# Controller.net
KiCad netlist of a schematic drawn in Altium Designer
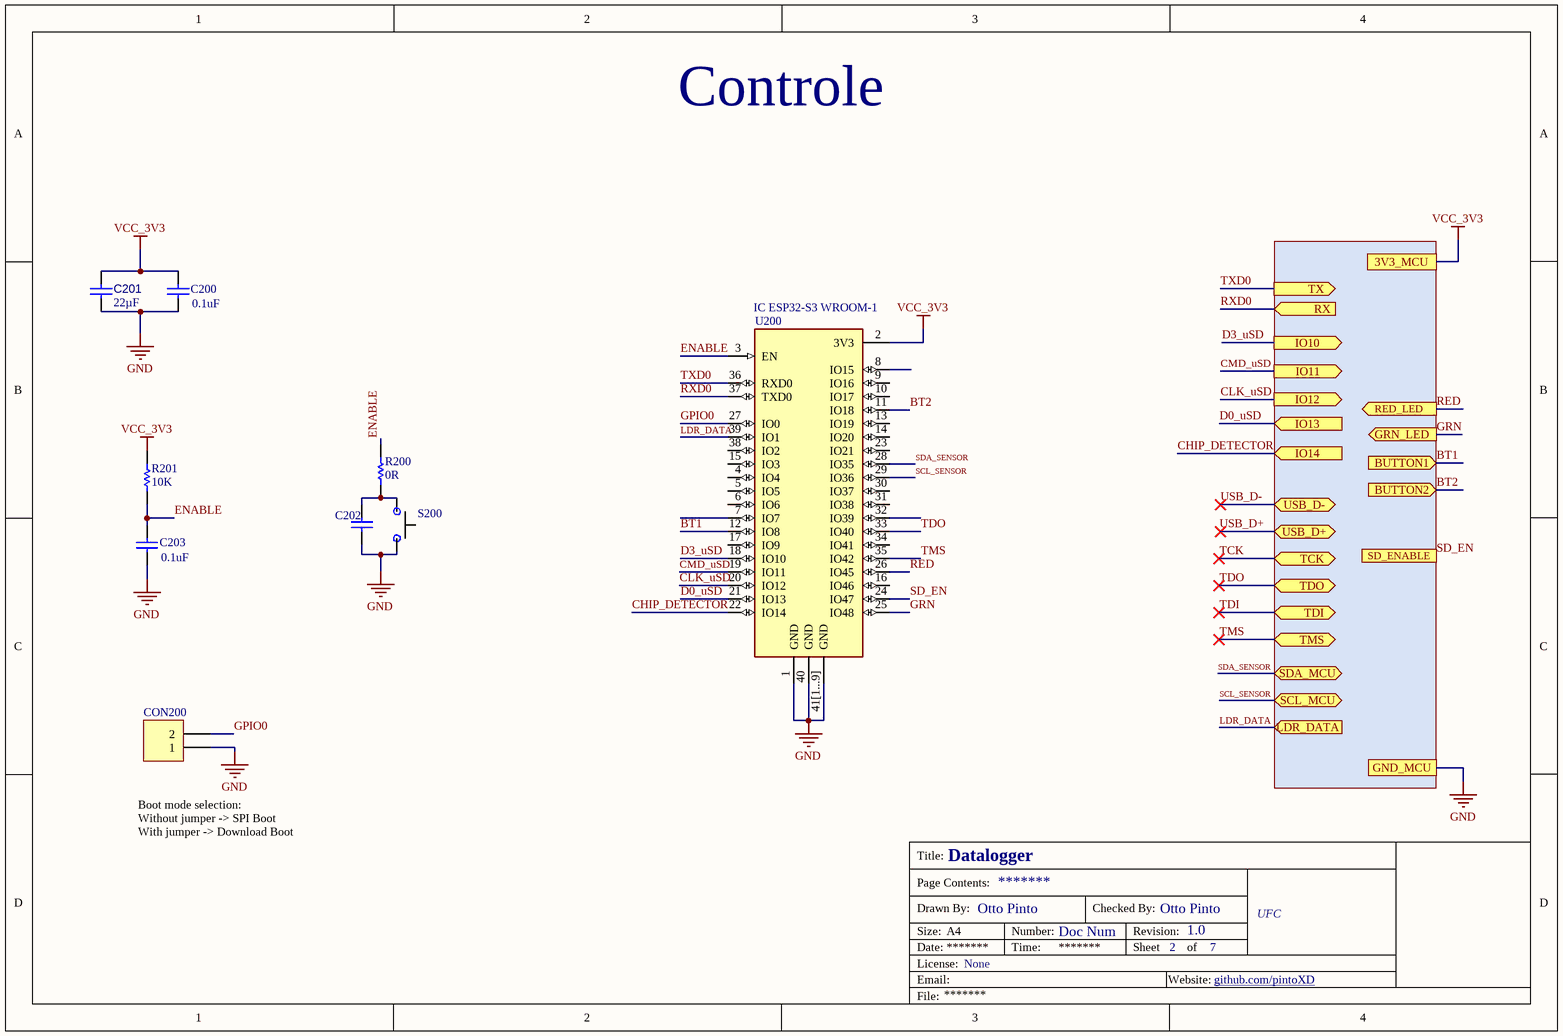
[diagram p0: Controller.SchDoc]

(export (version "E")
  (design (tool "Eeschema 10.0.6"))
  (components
    (comp (ref "C200")
      (value "0.1uF")
      (footprint "CC2012-0805")
      (description "Cap Ceramic 0.1uF 25V X7R 10% SMD 0805 125C Plastic T/R")
      (fields
        (field (name "MANUFACTURER") "KEMET")
        (field (name "MANUFACTURER PART NUMBER") "C0805C104K3RACTU")
      )
      (libsource (lib "lib_datalogger") (part "CAP CER 0.1uF 25V 0805 SMD"))
    )
    (comp (ref "C201")
      (value "22µF")
      (footprint "CC2012-0805")
      (description "Chip Capacitor, 22µF +/-40%, 16V, 0805, Thickness 1.45 mm")
      (fields (field (name "TOLERANCE") "5%") (field (name "Comment") "Capacitor 22µF +/-40% 16V 0805"))
      (libsource (lib "Mobit Brasil Ltda") (part "CAP-NP-2"))
    )
    (comp (ref "C202")
      (value "CAP CER 0.1uF 100V X7R SMD 0805")
      (footprint "CC2012-0805")
      (description "Cap Ceramic 0.1uF 25V X7R 10% SMD 0805 125C Plastic T/R")
      (fields
        (field (name "MANUFACTURER") "KEMET")
        (field (name "MANUFACTURER PART NUMBER") "C0805C104K3RACTU")
      )
      (libsource (lib "lib_datalogger") (part "CAP CER 0.1uF 25V 0805 SMD"))
    )
    (comp (ref "C203")
      (value "0.1uF")
      (footprint "CC2012-0805")
      (description "Cap Ceramic 0.1uF 25V X7R 10% SMD 0805 125C Plastic T/R")
      (fields
        (field (name "MANUFACTURER") "KEMET")
        (field (name "MANUFACTURER PART NUMBER") "C0805C104K3RACTU")
      )
      (libsource (lib "lib_datalogger") (part "CAP CER 0.1uF 25V 0805 SMD"))
    )
    (comp (ref "CON200")
      (value "PIN HEADER 2POS")
      (footprint "FP-TSW-102-07-G-S-MFG")
      (description "Conn Unshrouded Header HDR 2 POS 2.54mm Solder ST Top Entry Thru-Hole Bulk")
      (fields (field (name "MANUFACTURER PART NUMBER") "TSW-102-07-G-S"))
      (libsource (lib "Mobit Brasil Ltda") (part "Pin Header 2POS"))
    )
    (comp (ref "R200")
      (value "0R")
      (footprint "RESC2013X50X35ML15T15")
      (description "Chip Resistor, 0 Ohm, +/- 1%, 125 mW, -55 to 155 degC, 0805 (2012 Metric)")
      (fields (field (name "POWER") "125mW") (field (name "TOLERANCE") "1%"))
      (libsource (lib "Mobit Brasil Ltda") (part "RES-2"))
    )
    (comp (ref "R201")
      (value "10K")
      (footprint "CR2012-0805")
      (description "RES 0805 10K Ohm 0.1% 1/10W  SMD")
      (fields
        (field (name "MANUFACTURER PART NUMBER") "ERJ-6ENF1002V")
        (field (name "MANUFACTURER") "Panasonic Electronic Components")
        (field (name "SOURCE") "mits.SchLib")
      )
      (libsource (lib "Mobit Brasil Ltda") (part "Symbol"))
    )
    (comp (ref "S200")
      (value "SWITCH TACTILE SPST-NO 0.05A 12V SMD")
      (footprint "SWITCH_TACTILE_SMD_2PIN")
      (description "Switch Tactile N.O. SPST Rectangular Button J-Lead 0.05A 12VDC 2.55N SMD T/R")
      (fields
        (field (name "MANUFACTURER PART NUMBER") "TL3302BF260QJ")
        (field (name "MANUFACTURER") "E-Switch")
        (field (name "SOURCE") "mits.SchLib")
      )
      (libsource (lib "Mobit Brasil Ltda") (part "SWITCH TACTILE SPST-NO 0.05A 12V SMD"))
    )
    (comp (ref "U200")
      (value "IC ESP32-S3 WROOM-1")
      (footprint "ESP32_S3_WROOM_1")
      (description "SMD Module, ESP32-S3R2 With 8 MB of Flash")
      (fields
        (field (name "MF") "Espressif Systems")
        (field (name "MANUFACTURER PART NUMBER") "ESP32-S3-WROOM-1-N8")
      )
      (libsource (lib "lib_datalogger") (part "IC ESP32 S3 WROOM-1_v2"))
    )
  )
  (nets
    (net (code "1") (name "/BT1") (class "Default")
      (node (ref "U200") (pin "12") (pinfunction "IO8_12") (pintype "bidirectional"))
    )
    (net (code "2") (name "/BT2") (class "Default")
      (node (ref "U200") (pin "11") (pinfunction "IO18_11") (pintype "bidirectional"))
    )
    (net (code "3") (name "/CHIP_DETECTOR") (class "Default")
      (node (ref "U200") (pin "22") (pinfunction "IO14_22") (pintype "bidirectional"))
    )
    (net (code "4") (name "/CLK_uSD") (class "Default")
      (node (ref "U200") (pin "20") (pinfunction "IO12_20") (pintype "bidirectional"))
    )
    (net (code "5") (name "/CMD_uSD") (class "Default")
      (node (ref "U200") (pin "19") (pinfunction "IO11_19") (pintype "bidirectional"))
    )
    (net (code "6") (name "/D0_uSD") (class "Default")
      (node (ref "U200") (pin "21") (pinfunction "IO13_21") (pintype "bidirectional"))
    )
    (net (code "7") (name "/D3_uSD") (class "Default")
      (node (ref "U200") (pin "18") (pinfunction "IO10_18") (pintype "bidirectional"))
    )
    (net (code "8") (name "/ENABLE") (class "Default")
      (node (ref "C203") (pin "2") (pinfunction "2_2") (pintype "passive"))
      (node (ref "R200") (pin "2") (pinfunction "2_2") (pintype "passive"))
      (node (ref "R201") (pin "1") (pinfunction "1_1") (pintype "passive"))
      (node (ref "U200") (pin "3") (pinfunction "EN_3") (pintype "input"))
    )
    (net (code "9") (name "/GPIO0") (class "Default")
      (node (ref "CON200") (pin "2") (pinfunction "2_2") (pintype "passive"))
      (node (ref "U200") (pin "27") (pinfunction "IO0_27") (pintype "bidirectional"))
    )
    (net (code "10") (name "/GRN") (class "Default")
      (node (ref "U200") (pin "25") (pinfunction "IO48_25") (pintype "bidirectional"))
    )
    (net (code "11") (name "/LDR_DATA") (class "Default")
      (node (ref "U200") (pin "39") (pinfunction "IO1_39") (pintype "bidirectional"))
    )
    (net (code "12") (name "/RED") (class "Default")
      (node (ref "U200") (pin "26") (pinfunction "IO45_26") (pintype "bidirectional"))
    )
    (net (code "13") (name "/RXD0") (class "Default")
      (node (ref "U200") (pin "37") (pinfunction "TXD0_37") (pintype "bidirectional"))
    )
    (net (code "14") (name "/SCL_SENSOR") (class "Default")
      (node (ref "U200") (pin "29") (pinfunction "IO36_29") (pintype "bidirectional"))
    )
    (net (code "15") (name "/SDA_SENSOR") (class "Default")
      (node (ref "U200") (pin "28") (pinfunction "IO35_28") (pintype "bidirectional"))
    )
    (net (code "16") (name "/SD_EN") (class "Default")
      (node (ref "U200") (pin "24") (pinfunction "IO47_24") (pintype "bidirectional"))
    )
    (net (code "19") (name "/TDO") (class "Default")
      (node (ref "U200") (pin "33") (pinfunction "IO40_33") (pintype "bidirectional"))
    )
    (net (code "20") (name "/TMS") (class "Default")
      (node (ref "U200") (pin "35") (pinfunction "IO42_35") (pintype "bidirectional+no_connect"))
    )
    (net (code "21") (name "/TXD0") (class "Default")
      (node (ref "U200") (pin "36") (pinfunction "RXD0_36") (pintype "bidirectional"))
    )
    (net (code "24") (name "GND") (class "Default")
      (node (ref "C200") (pin "1") (pinfunction "1_1") (pintype "passive"))
      (node (ref "C201") (pin "1") (pinfunction "1_1") (pintype "passive"))
      (node (ref "C202") (pin "1") (pinfunction "1_1") (pintype "passive"))
      (node (ref "C203") (pin "1") (pinfunction "1_1") (pintype "passive"))
      (node (ref "CON200") (pin "1") (pinfunction "1_1") (pintype "passive"))
      (node (ref "S200") (pin "1") (pinfunction "1_1") (pintype "passive"))
      (node (ref "U200") (pin "1") (pinfunction "GND_1") (pintype "power_in"))
      (node (ref "U200") (pin "40") (pinfunction "GND_40") (pintype "power_in"))
      (node (ref "U200") (pin "41[1...9]") (pinfunction "GND_41[1...9]") (pintype "power_in"))
    )
    (net (code "25") (name "Net-(C202-Pad2)") (class "Default")
      (node (ref "C202") (pin "2") (pinfunction "2_2") (pintype "passive"))
      (node (ref "R200") (pin "1") (pinfunction "1_1") (pintype "passive"))
      (node (ref "S200") (pin "2") (pinfunction "2_2") (pintype "passive"))
    )
    (net (code "26") (name "VCC_3V3") (class "Default")
      (node (ref "C200") (pin "2") (pinfunction "2_2") (pintype "passive"))
      (node (ref "C201") (pin "2") (pinfunction "2_2") (pintype "passive"))
      (node (ref "R201") (pin "2") (pinfunction "2_2") (pintype "passive"))
      (node (ref "U200") (pin "2") (pinfunction "3V3_2") (pintype "power_in"))
    )
    (net (code "27") (name "unconnected-(U200-IO2-Pad38)") (class "Default")
      (node (ref "U200") (pin "38") (pinfunction "IO2_38") (pintype "bidirectional"))
    )
    (net (code "28") (name "unconnected-(U200-IO3-Pad15)") (class "Default")
      (node (ref "U200") (pin "15") (pinfunction "IO3_15") (pintype "bidirectional"))
    )
    (net (code "29") (name "unconnected-(U200-IO4-Pad4)") (class "Default")
      (node (ref "U200") (pin "4") (pinfunction "IO4_4") (pintype "bidirectional"))
    )
    (net (code "30") (name "unconnected-(U200-IO5-Pad5)") (class "Default")
      (node (ref "U200") (pin "5") (pinfunction "IO5_5") (pintype "bidirectional"))
    )
    (net (code "31") (name "unconnected-(U200-IO6-Pad6)") (class "Default")
      (node (ref "U200") (pin "6") (pinfunction "IO6_6") (pintype "bidirectional"))
    )
    (net (code "32") (name "unconnected-(U200-IO7-Pad7)") (class "Default")
      (node (ref "U200") (pin "7") (pinfunction "IO7_7") (pintype "bidirectional"))
    )
    (net (code "33") (name "unconnected-(U200-IO9-Pad17)") (class "Default")
      (node (ref "U200") (pin "17") (pinfunction "IO9_17") (pintype "bidirectional"))
    )
    (net (code "34") (name "unconnected-(U200-IO15-Pad8)") (class "Default")
      (node (ref "U200") (pin "8") (pinfunction "IO15_8") (pintype "bidirectional"))
    )
    (net (code "35") (name "unconnected-(U200-IO16-Pad9)") (class "Default")
      (node (ref "U200") (pin "9") (pinfunction "IO16_9") (pintype "bidirectional"))
    )
    (net (code "36") (name "unconnected-(U200-IO17-Pad10)") (class "Default")
      (node (ref "U200") (pin "10") (pinfunction "IO17_10") (pintype "bidirectional"))
    )
    (net (code "37") (name "unconnected-(U200-IO19-Pad13)") (class "Default")
      (node (ref "U200") (pin "13") (pinfunction "IO19_13") (pintype "bidirectional"))
    )
    (net (code "38") (name "unconnected-(U200-IO20-Pad14)") (class "Default")
      (node (ref "U200") (pin "14") (pinfunction "IO20_14") (pintype "bidirectional"))
    )
    (net (code "39") (name "unconnected-(U200-IO21-Pad23)") (class "Default")
      (node (ref "U200") (pin "23") (pinfunction "IO21_23") (pintype "bidirectional"))
    )
    (net (code "40") (name "unconnected-(U200-IO37-Pad30)") (class "Default")
      (node (ref "U200") (pin "30") (pinfunction "IO37_30") (pintype "bidirectional"))
    )
    (net (code "41") (name "unconnected-(U200-IO38-Pad31)") (class "Default")
      (node (ref "U200") (pin "31") (pinfunction "IO38_31") (pintype "bidirectional"))
    )
    (net (code "42") (name "unconnected-(U200-IO39-Pad32)") (class "Default")
      (node (ref "U200") (pin "32") (pinfunction "IO39_32") (pintype "bidirectional"))
    )
    (net (code "43") (name "unconnected-(U200-IO41-Pad34)") (class "Default")
      (node (ref "U200") (pin "34") (pinfunction "IO41_34") (pintype "bidirectional"))
    )
    (net (code "44") (name "unconnected-(U200-IO46-Pad16)") (class "Default")
      (node (ref "U200") (pin "16") (pinfunction "IO46_16") (pintype "bidirectional"))
    )
  )
)
